# USB_OTG.net
KiCad netlist of a schematic drawn in Altium Designer
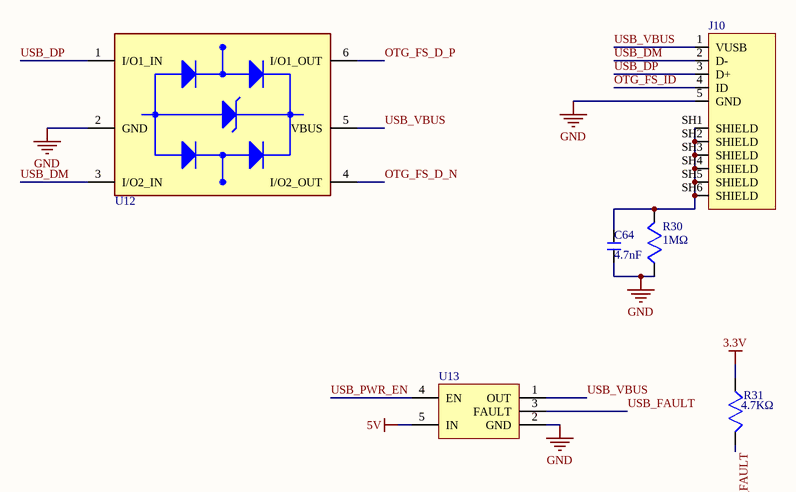
[diagram p0: USB_OTG.SchDoc]

(export (version "E")
  (design (tool "Eeschema 10.0.6"))
  (components
    (comp (ref "C64")
      (value "4.7nF")
      (footprint "402 capacitor - duplicate")
      (description "CAP SMD 402")
      (fields (field (name "MPN") "C0402C472K5RECAUTO") (field (name "Comment") "0402 capacitor"))
      (libsource (lib "Schlib1") (part "CAP SMD 402"))
    )
    (comp (ref "J10")
      (value "10118192-0001LF")
      (footprint "10118192-0001LF")
      (description "CONN RCPT USB2.0 MICRO B SMD R/A")
      (libsource (lib "Schlib1") (part "10118192-0001LF"))
    )
    (comp (ref "R30")
      (value "1MΩ")
      (footprint "402 RESISTOR")
      (description "RES SMD 0402")
      (fields (field (name "MPN") "CR0402JC1MS001") (field (name "Comment") "0402. RESİSTOR"))
      (libsource (lib "Schlib1") (part "RES SMD 0402"))
    )
    (comp (ref "R31")
      (value "4.7KΩ")
      (footprint "805 resistor")
      (description "RES SMD 0805")
      (fields (field (name "MPN") "RG2012L-472-L-T05") (field (name "Comment") "0805 resistor"))
      (libsource (lib "Schlib1") (part "RES SMD 0805"))
    )
    (comp (ref "U12")
      (value "USBLC6-2SC6")
      (footprint "USBLC6-2SC6")
      (description "TVS DIODE 5.25VWM 17VC SOT23-6")
      (libsource (lib "Schlib1") (part "USBLC6-2SC6"))
    )
    (comp (ref "U13")
      (value "STMPS2141STR")
      (footprint "STMPS2141STR")
      (description "IC PWR SWITCH N-CHAN 1:1 SOT23-5")
      (libsource (lib "Schlib1") (part "STMPS2141STR"))
    )
  )
  (nets
    (net (code "1") (name "/OTG_FS_D_N") (class "Default")
      (node (ref "U12") (pin "4") (pinfunction "I/O2_OUT_4") (pintype "power_in"))
    )
    (net (code "2") (name "/OTG_FS_D_P") (class "Default")
      (node (ref "U12") (pin "6") (pinfunction "I/O1_OUT_6") (pintype "power_in"))
    )
    (net (code "3") (name "/OTG_FS_ID") (class "Default")
      (node (ref "J10") (pin "4") (pinfunction "ID_4") (pintype "passive"))
    )
    (net (code "4") (name "/USB_DM") (class "Default")
      (node (ref "J10") (pin "2") (pinfunction "D-_2") (pintype "passive"))
      (node (ref "U12") (pin "3") (pinfunction "I/O2_IN_3") (pintype "power_in"))
    )
    (net (code "5") (name "/USB_DP") (class "Default")
      (node (ref "J10") (pin "3") (pinfunction "D+_3") (pintype "passive"))
      (node (ref "U12") (pin "1") (pinfunction "I/O1_IN_1") (pintype "power_in"))
    )
    (net (code "6") (name "/USB_FAULT") (class "Default")
      (node (ref "R31") (pin "2") (pintype "passive"))
      (node (ref "U13") (pin "3") (pinfunction "FAULT_3") (pintype "power_in"))
    )
    (net (code "7") (name "/USB_PWR_EN") (class "Default")
      (node (ref "U13") (pin "4") (pinfunction "EN_4") (pintype "power_in"))
    )
    (net (code "8") (name "/USB_VBUS") (class "Default")
      (node (ref "J10") (pin "1") (pinfunction "VUSB_1") (pintype "passive"))
      (node (ref "U12") (pin "5") (pinfunction "VBUS_5") (pintype "power_in"))
      (node (ref "U13") (pin "1") (pinfunction "OUT_1") (pintype "power_in"))
    )
    (net (code "9") (name "3.3V") (class "Default") (node (ref "R31") (pin "1") (pintype "passive")))
    (net (code "10") (name "5V") (class "Default")
      (node (ref "U13") (pin "5") (pinfunction "IN_5") (pintype "power_in"))
    )
    (net (code "11") (name "GND") (class "Default")
      (node (ref "C64") (pin "2") (pintype "passive"))
      (node (ref "J10") (pin "5") (pinfunction "GND_5") (pintype "passive"))
      (node (ref "R30") (pin "1") (pintype "passive"))
      (node (ref "U12") (pin "2") (pinfunction "GND_2") (pintype "power_in"))
      (node (ref "U13") (pin "2") (pinfunction "GND_2") (pintype "power_in"))
    )
    (net (code "12") (name "Net-(C64-Pad1)") (class "Default")
      (node (ref "C64") (pin "1") (pintype "passive"))
      (node (ref "J10") (pin "SH1") (pinfunction "SHIELD_SH1") (pintype "passive"))
      (node (ref "J10") (pin "SH2") (pinfunction "SHIELD_SH2") (pintype "passive"))
      (node (ref "J10") (pin "SH3") (pinfunction "SHIELD_SH3") (pintype "passive"))
      (node (ref "J10") (pin "SH4") (pinfunction "SHIELD_SH4") (pintype "passive"))
      (node (ref "J10") (pin "SH5") (pinfunction "SHIELD_SH5") (pintype "passive"))
      (node (ref "J10") (pin "SH6") (pinfunction "SHIELD_SH6") (pintype "passive"))
      (node (ref "R30") (pin "2") (pintype "passive"))
    )
  )
)
